# main.net
KiCad netlist of a schematic drawn in Altium Designer
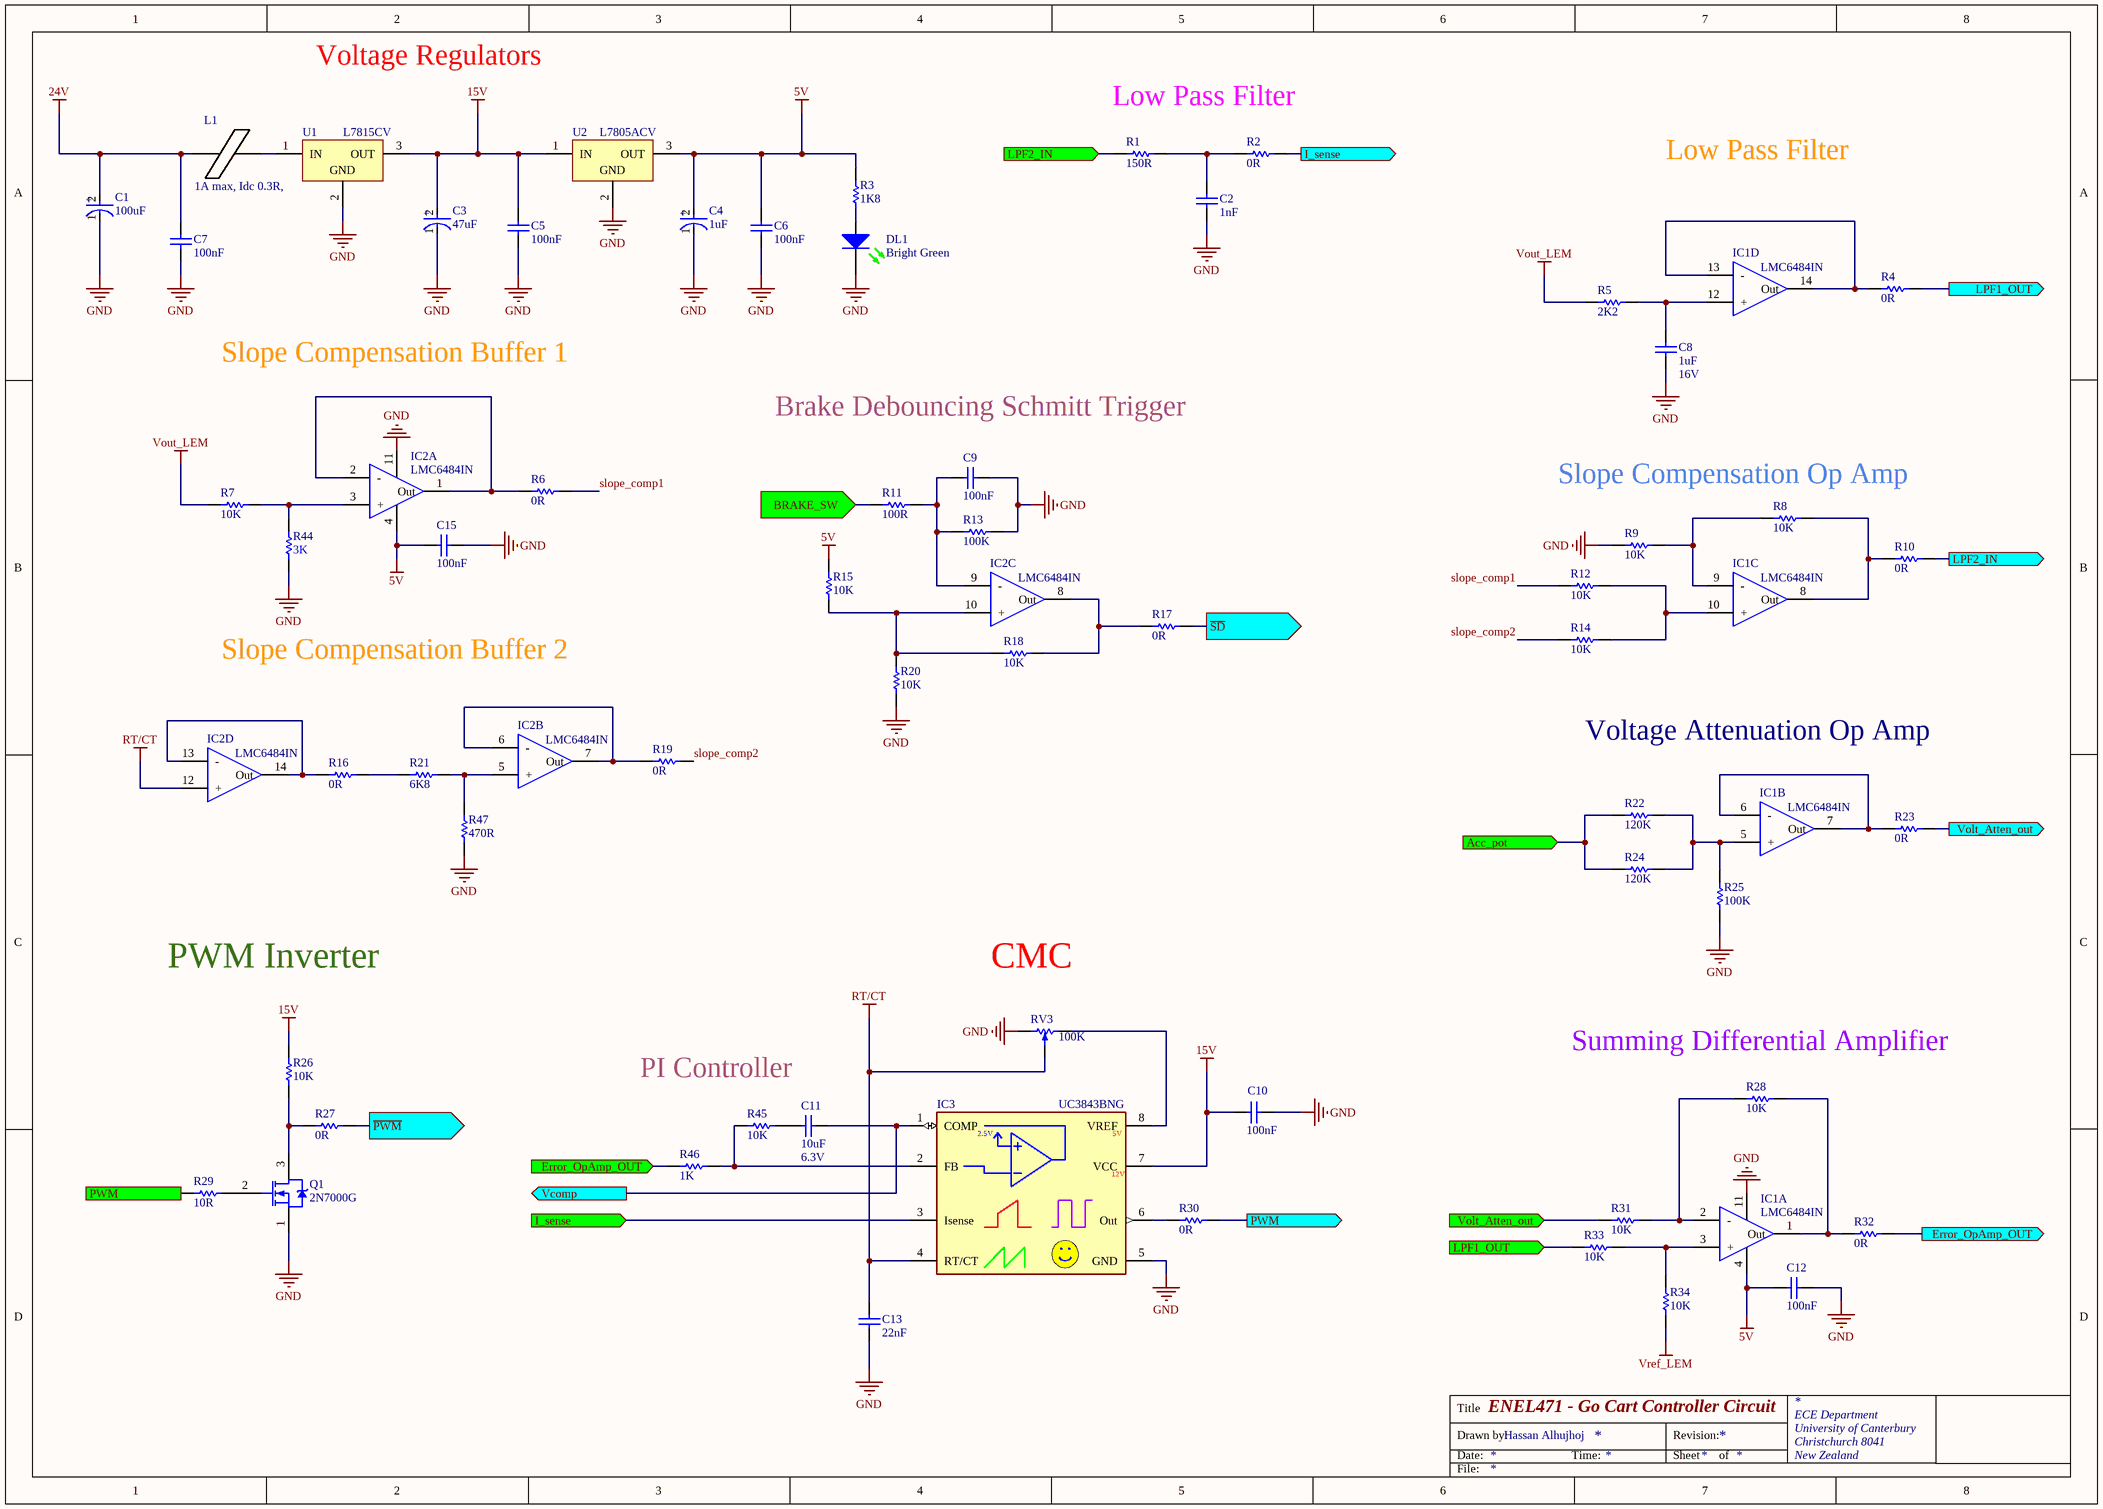
[diagram p0: main.SchDoc]

(export (version "E")
  (design (tool "Eeschema 10.0.6"))
  (components
    (comp (ref "C1")
      (value "100uF")
      (footprint "FP-ESLGM-MFG")
      (description "CAP ALUM 100UF 20% 50V THRU HOLE. Part Number: ESL107M050AGMAA. Dia: 8mm.")
      (fields
        (field (name "TOLERANCE") "20%")
        (field (name "OCTOPART") "https://octopart.com/esl107m050agmaa-kemet-84758890")
      )
      (libsource (lib "Altium Content Vault") (part "a00bbbee19879c290e62620ae7e47b1"))
    )
    (comp (ref "C2")
      (value "1nF")
      (footprint "CAPC1608L")
      (description "CAP CER 1nF X7R +-10% 50V 0603")
      (libsource (lib "ECE AD19Components_19V1") (part "CC_1nF_0603"))
    )
    (comp (ref "C3")
      (value "47uF")
      (footprint "FP-ESLE3-MFG")
      (description "CAP ALUM 10UF 20% 100V THRU HOLE. Part Number: ESL106M100AE3AA. Dia: 6.3mm.")
      (fields (field (name "TOLERANCE") "20%") (field (name "MANUFACTURER PART NUMBER") "ESL106M100AE3AA"))
      (libsource (lib "Altium Content Vault") (part "cf48714ba7e38822c1575c7ec0b6d1f"))
    )
    (comp (ref "C4")
      (value "1uF")
      (footprint "FP-UPW1E220MDD-MFG")
      (description "CAP ALUM 22UF 20% 25V RADIAL. Part Number: UPW1E220MDD. Dia: 5mm.")
      (fields
        (field (name "OCTOPART") "https://octopart.com/upw1e220mdd-nichicon-202818")
        (field (name "TOLERANCE") "20%")
      )
      (libsource (lib "Altium Content Vault") (part "cf48714ba7e38822c1575c7ec0b6d1f"))
    )
    (comp (ref "C5")
      (value "100nF")
      (footprint "CAPC1608L")
      (description "CAP CER 100nF X7R +-10% 50V 0603")
      (libsource (lib "ECE AD19Components_19V1") (part "CC_100nF_0603"))
    )
    (comp (ref "C6")
      (value "100nF")
      (footprint "CAPC1608L")
      (description "CAP CER 100nF X7R +-10% 50V 0603")
      (libsource (lib "ECE AD19Components_19V1") (part "CC_100nF_0603"))
    )
    (comp (ref "C7")
      (value "100nF")
      (footprint "CAPC1608L")
      (description "CAP CER 100nF X7R +-10% 50V 0603")
      (libsource (lib "ECE AD19Components_19V1") (part "CC_100nF_0603"))
    )
    (comp (ref "C8")
      (value "1uF")
      (footprint "CAPC1608L")
      (description "CAP CER 1uF Y5V -20% +80% 16V 0603")
      (fields (field (name "MAX VOLTAGE") "16V"))
      (libsource (lib "ECE AD19Components_19V1") (part "CC_1uF_0603"))
    )
    (comp (ref "C9")
      (value "100nF")
      (footprint "CAPC1608L")
      (description "CAP CER 100nF X7R +-10% 50V 0603")
      (libsource (lib "ECE AD19Components_19V1") (part "CC_100nF_0603"))
    )
    (comp (ref "C10")
      (value "100nF")
      (footprint "CAPC1608L")
      (description "CAP CER 100nF X7R +-10% 50V 0603")
      (libsource (lib "ECE AD19Components_19V1") (part "CC_100nF_0603"))
    )
    (comp (ref "C11")
      (value "10uF")
      (footprint "CAPC1608L")
      (description "CAP CER 10UF X5R +-20% 6V3 0603")
      (fields (field (name "VOLTAGE - RATED") "6.3V"))
      (libsource (lib "ECE AD19Components_19V1") (part "CC_10uF_0603"))
    )
    (comp (ref "C12")
      (value "100nF")
      (footprint "CAPC1608L")
      (description "CAP CER 100nF X7R +-10% 50V 0603")
      (libsource (lib "ECE AD19Components_19V1") (part "CC_100nF_0603"))
    )
    (comp (ref "C13")
      (value "22nF")
      (footprint "CAPC1608L")
      (description "CAP CER 22nF X7R +-10% 50V 0603")
      (libsource (lib "ECE AD19Components_19V1") (part "CC_22nF_0603"))
    )
    (comp (ref "C15")
      (value "100nF")
      (footprint "CAPC1608L")
      (description "CAP CER 100nF X7R +-10% 50V 0603")
      (libsource (lib "ECE AD19Components_19V1") (part "CC_100nF_0603"))
    )
    (comp (ref "DL1")
      (value "Bright Green")
      (footprint "WL-SMCW0603")
      (description "LED Bright Green 40mcd 0603 SMD")
      (fields
        (field (name "MANUFACTURER") "WURTH ELEKTRONIK")
        (field (name "MANUFACTURER PART NUMBER") "150060VS75000")
        (field (name "LED COLOUR") "Bright Green")
      )
      (libsource (lib "ECE AD19Components_19V1") (part "DL_150060VS75000"))
    )
    (comp (ref "IC1")
      (value "LMC6484IN")
      (footprint "SamacSys:DIP794W56P254L1905H533Q14N")
      (description "Integrated Circuit")
      (fields (field (name "MOUSER PART NUMBER") "926-LMC6484IN"))
      (libsource (lib "SamacSys") (part "LMC6484IN"))
    )
    (comp (ref "IC2")
      (value "LMC6484IN")
      (footprint "SamacSys:DIP794W56P254L1905H533Q14N")
      (description "Integrated Circuit")
      (fields (field (name "MOUSER PART NUMBER") "926-LMC6484IN"))
      (libsource (lib "SamacSys") (part "LMC6484IN"))
    )
    (comp (ref "IC3")
      (value "UC3843BNG")
      (footprint "SamacSys:DIP794W56P254L959H533Q8B")
      (description "Integrated Circuit")
      (fields (field (name "MOUSER PART NUMBER") "863-UC3843BNG"))
      (libsource (lib "SamacSys") (part "UC3843BNG"))
    )
    (comp (ref "L1")
      (value "1A max, Idc 0.3R,")
      (footprint "INDC3216L")
      (description "Ferrite Bead, Rdc 0.3R, Z100MHZ 600R, Imax 1A, SMD 1206")
      (fields
        (field (name "MANUFACTURER") "FAIR-RITE")
        (field (name "MANUFACTURER PART NUMBER") "2512066017Y1")
      )
      (libsource (lib "ECE AD19Components_19V1") (part "IN_Ferrite-Bead"))
    )
    (comp (ref "Q1")
      (value "2N7000G")
      (footprint "ONSC-TO-92-3-29-11")
      (description "Small Signal MOSFET, 200 mA, 60 V, N-Channel, 3-Pin TO-92, Pb-Free, Bulk Box")
      (fields (field (name "MANUFACTURER") "On Semiconductor"))
      (libsource (lib "Altium Content Vault") (part "ONSC-NMOS-S1G2D3-3"))
    )
    (comp (ref "R1")
      (value "150R")
      (footprint "RESC1608L")
      (description "RES 150 OHM 1/10W 5% 0603 SMD")
      (libsource (lib "ECE AD19Components_19V1") (part "RS_150R"))
    )
    (comp (ref "R2")
      (value "0R")
      (footprint "RESC1608L")
      (description "RES 0.0 OHM 1/10W 5% 0603 SMD")
      (libsource (lib "ECE AD19Components_19V1") (part "RS_0R0"))
    )
    (comp (ref "R3")
      (value "1K8")
      (footprint "RESC1608L")
      (description "RES 1.8K OHM 1/10W 5% 0603 SMD")
      (libsource (lib "ECE AD19Components_19V1") (part "RS_1K8"))
    )
    (comp (ref "R4")
      (value "0R")
      (footprint "RESC1608L")
      (description "RES 0.0 OHM 1/10W 5% 0603 SMD")
      (libsource (lib "ECE AD19Components_19V1") (part "RS_0R0"))
    )
    (comp (ref "R5")
      (value "2K2")
      (footprint "RESC1608L")
      (description "RES 2.2K OHM 1/10W 5% 0603 SMD")
      (libsource (lib "ECE AD19Components_19V1") (part "RS_2K2"))
    )
    (comp (ref "R6")
      (value "0R")
      (footprint "RESC1608L")
      (description "RES 0.0 OHM 1/10W 5% 0603 SMD")
      (libsource (lib "ECE AD19Components_19V1") (part "RS_0R0"))
    )
    (comp (ref "R7")
      (value "10K")
      (footprint "RESC1608L")
      (description "RES 10.0K OHM 1/10W 5% 0603 SMD")
      (libsource (lib "ECE AD19Components_19V1") (part "RS_10K"))
    )
    (comp (ref "R8")
      (value "10K")
      (footprint "RESC1608L")
      (description "RES 10.0K OHM 1/10W 5% 0603 SMD")
      (libsource (lib "ECE AD19Components_19V1") (part "RS_10K"))
    )
    (comp (ref "R9")
      (value "10K")
      (footprint "RESC1608L")
      (description "RES 10.0K OHM 1/10W 5% 0603 SMD")
      (libsource (lib "ECE AD19Components_19V1") (part "RS_10K"))
    )
    (comp (ref "R10")
      (value "0R")
      (footprint "RESC1608L")
      (description "RES 0.0 OHM 1/10W 5% 0603 SMD")
      (libsource (lib "ECE AD19Components_19V1") (part "RS_0R0"))
    )
    (comp (ref "R11")
      (value "100R")
      (footprint "RESC1608L")
      (description "RES 100 OHM 1/10W 5% 0603 SMD")
      (libsource (lib "ECE AD19Components_19V1") (part "RS_100R"))
    )
    (comp (ref "R12")
      (value "10K")
      (footprint "RESC1608L")
      (description "RES 10.0K OHM 1/10W 5% 0603 SMD")
      (libsource (lib "ECE AD19Components_19V1") (part "RS_10K"))
    )
    (comp (ref "R13")
      (value "100K")
      (footprint "RESC1608L")
      (description "RES 100K OHM 1/10W 5% 0603 SMD")
      (libsource (lib "ECE AD19Components_19V1") (part "RS_100K"))
    )
    (comp (ref "R14")
      (value "10K")
      (footprint "RESC1608L")
      (description "RES 10.0K OHM 1/10W 5% 0603 SMD")
      (libsource (lib "ECE AD19Components_19V1") (part "RS_10K"))
    )
    (comp (ref "R15")
      (value "10K")
      (footprint "RESC1608L")
      (description "RES 10.0K OHM 1/10W 5% 0603 SMD")
      (libsource (lib "ECE AD19Components_19V1") (part "RS_10K"))
    )
    (comp (ref "R16")
      (value "0R")
      (footprint "RESC1608L")
      (description "RES 0.0 OHM 1/10W 5% 0603 SMD")
      (libsource (lib "ECE AD19Components_19V1") (part "RS_0R0"))
    )
    (comp (ref "R17")
      (value "0R")
      (footprint "RESC1608L")
      (description "RES 0.0 OHM 1/10W 5% 0603 SMD")
      (libsource (lib "ECE AD19Components_19V1") (part "RS_0R0"))
    )
    (comp (ref "R18")
      (value "10K")
      (footprint "RESC1608L")
      (description "RES 10.0K OHM 1/10W 5% 0603 SMD")
      (libsource (lib "ECE AD19Components_19V1") (part "RS_10K"))
    )
    (comp (ref "R19")
      (value "0R")
      (footprint "RESC1608L")
      (description "RES 0.0 OHM 1/10W 5% 0603 SMD")
      (libsource (lib "ECE AD19Components_19V1") (part "RS_0R0"))
    )
    (comp (ref "R20")
      (value "10K")
      (footprint "RESC1608L")
      (description "RES 10.0K OHM 1/10W 5% 0603 SMD")
      (libsource (lib "ECE AD19Components_19V1") (part "RS_10K"))
    )
    (comp (ref "R21")
      (value "6K8")
      (footprint "RESC1608L")
      (description "RES 6k8 OHM 1/10W 5% 0603 SMD")
      (libsource (lib "ECE AD19Components_19V1") (part "RS_6K8"))
    )
    (comp (ref "R22")
      (value "120K")
      (footprint "RESC1608L")
      (description "RES 120K OHM 1/10W 5% 0603 SMD")
      (libsource (lib "ECE AD19Components_19V1") (part "RS_120K"))
    )
    (comp (ref "R23")
      (value "0R")
      (footprint "RESC1608L")
      (description "RES 0.0 OHM 1/10W 5% 0603 SMD")
      (libsource (lib "ECE AD19Components_19V1") (part "RS_0R0"))
    )
    (comp (ref "R24")
      (value "120K")
      (footprint "RESC1608L")
      (description "RES 120K OHM 1/10W 5% 0603 SMD")
      (libsource (lib "ECE AD19Components_19V1") (part "RS_120K"))
    )
    (comp (ref "R25")
      (value "100K")
      (footprint "RESC1608L")
      (description "RES 100K OHM 1/10W 5% 0603 SMD")
      (libsource (lib "ECE AD19Components_19V1") (part "RS_100K"))
    )
    (comp (ref "R26")
      (value "10K")
      (footprint "RESC1608L")
      (description "RES 10.0K OHM 1/10W 5% 0603 SMD")
      (libsource (lib "ECE AD19Components_19V1") (part "RS_10K"))
    )
    (comp (ref "R27")
      (value "0R")
      (footprint "RESC1608L")
      (description "RES 0.0 OHM 1/10W 5% 0603 SMD")
      (libsource (lib "ECE AD19Components_19V1") (part "RS_0R0"))
    )
    (comp (ref "R28")
      (value "10K")
      (footprint "RESC1608L")
      (description "RES 10.0K OHM 1/10W 5% 0603 SMD")
      (libsource (lib "ECE AD19Components_19V1") (part "RS_10K"))
    )
    (comp (ref "R29")
      (value "10R")
      (footprint "RESC1608L")
      (description "RES 10 OHM 1/10W 5% 0603 SMD")
      (libsource (lib "ECE AD19Components_19V1") (part "RS_10R"))
    )
    (comp (ref "R30")
      (value "0R")
      (footprint "RESC1608L")
      (description "RES 0.0 OHM 1/10W 5% 0603 SMD")
      (libsource (lib "ECE AD19Components_19V1") (part "RS_0R0"))
    )
    (comp (ref "R31")
      (value "10K")
      (footprint "RESC1608L")
      (description "RES 10.0K OHM 1/10W 5% 0603 SMD")
      (libsource (lib "ECE AD19Components_19V1") (part "RS_10K"))
    )
    (comp (ref "R32")
      (value "0R")
      (footprint "RESC1608L")
      (description "RES 0.0 OHM 1/10W 5% 0603 SMD")
      (libsource (lib "ECE AD19Components_19V1") (part "RS_0R0"))
    )
    (comp (ref "R33")
      (value "10K")
      (footprint "RESC1608L")
      (description "RES 10.0K OHM 1/10W 5% 0603 SMD")
      (libsource (lib "ECE AD19Components_19V1") (part "RS_10K"))
    )
    (comp (ref "R34")
      (value "10K")
      (footprint "RESC1608L")
      (description "RES 10.0K OHM 1/10W 5% 0603 SMD")
      (libsource (lib "ECE AD19Components_19V1") (part "RS_10K"))
    )
    (comp (ref "R44")
      (value "3K")
      (footprint "RESC1608L")
      (description "RES 3K OHM 1/10W 5% 0603 SMD")
      (libsource (lib "ECE AD19Components_19V1") (part "RS_3K"))
    )
    (comp (ref "R45")
      (value "10K")
      (footprint "RESC1608L")
      (description "RES 10.0K OHM 1/10W 5% 0603 SMD")
      (libsource (lib "ECE AD19Components_19V1") (part "RS_10K"))
    )
    (comp (ref "R46")
      (value "1K")
      (footprint "RESC1608L")
      (description "RES 1.0K OHM 1/10W 5% 0603 SMD")
      (libsource (lib "ECE AD19Components_19V1") (part "RS_1K"))
    )
    (comp (ref "R47")
      (value "470R")
      (footprint "RESC1608L")
      (description "RES 470 OHM 1/10W 5% 0603 SMD")
      (libsource (lib "ECE AD19Components_19V1") (part "RS_470R"))
    )
    (comp (ref "RV3")
      (value "100K")
      (footprint "PVZ2A")
      (description "Trim Pot SMD 100K Murata PVZ2 Series SMD")
      (fields
        (field (name "MANUFACTURER") "MURATA")
        (field (name "MANUFACTURER PART NUMBER") "PVZ2A104C04B00")
      )
      (libsource (lib "ECE AD19Components_19V1") (part "RM_100K"))
    )
    (comp (ref "U1")
      (value "L7815CV")
      (footprint "TO220")
      (description "Positive Voltage Regulator, 15V, 3-Pin TO-220")
      (libsource (lib "Altium Content Vault") (part "PM-REG-L4940-SIL3"))
    )
    (comp (ref "U2")
      (value "L7805ACV")
      (footprint "TO220")
      (description "Positive Voltage Regulator, 5V, 3-Pin TO-220")
      (libsource (lib "Altium Content Vault") (part "PM-REG-L4940-SIL3"))
    )
  )
  (nets
    (net (code "1") (name "/Acc_pot") (class "Default")
      (node (ref "R22") (pin "2") (pinfunction "2_2") (pintype "passive"))
      (node (ref "R24") (pin "1") (pinfunction "1_1") (pintype "passive"))
    )
    (net (code "2") (name "/BRAKE_SW") (class "Default")
      (node (ref "R11") (pin "1") (pinfunction "1_1") (pintype "passive"))
    )
    (net (code "3") (name "/Error_OpAmp_OUT") (class "Default")
      (node (ref "R32") (pin "2") (pinfunction "2_2") (pintype "passive"))
      (node (ref "R46") (pin "1") (pinfunction "1_1") (pintype "passive"))
    )
    (net (code "4") (name "/I_sense") (class "Default")
      (node (ref "IC3") (pin "3") (pinfunction "Isense_3") (pintype "passive"))
      (node (ref "R2") (pin "2") (pinfunction "2_2") (pintype "passive"))
    )
    (net (code "5") (name "/LPF1_OUT") (class "Default")
      (node (ref "R33") (pin "1") (pinfunction "1_1") (pintype "passive"))
      (node (ref "R4") (pin "2") (pinfunction "2_2") (pintype "passive"))
    )
    (net (code "6") (name "/LPF2_IN") (class "Default")
      (node (ref "R1") (pin "1") (pinfunction "1_1") (pintype "passive"))
      (node (ref "R10") (pin "2") (pinfunction "2_2") (pintype "passive"))
    )
    (net (code "7") (name "/PWM") (class "Default")
      (node (ref "R29") (pin "1") (pinfunction "1_1") (pintype "passive"))
      (node (ref "R30") (pin "2") (pinfunction "2_2") (pintype "passive"))
    )
    (net (code "8") (name "/Vcomp") (class "Default")
      (node (ref "C11") (pin "1") (pinfunction "1_1") (pintype "passive"))
      (node (ref "IC3") (pin "1") (pinfunction "COMP_1") (pintype "bidirectional"))
    )
    (net (code "9") (name "/Volt_Atten_out") (class "Default")
      (node (ref "R23") (pin "2") (pinfunction "2_2") (pintype "passive"))
      (node (ref "R31") (pin "1") (pinfunction "1_1") (pintype "passive"))
    )
    (net (code "10") (name "/slope_comp1") (class "Default")
      (node (ref "R12") (pin "1") (pinfunction "1_1") (pintype "passive"))
      (node (ref "R6") (pin "2") (pinfunction "2_2") (pintype "passive"))
    )
    (net (code "11") (name "/slope_comp2") (class "Default")
      (node (ref "R14") (pin "1") (pinfunction "1_1") (pintype "passive"))
      (node (ref "R19") (pin "2") (pinfunction "2_2") (pintype "passive"))
    )
    (net (code "12") (name "/~{PWM}") (class "Default")
      (node (ref "R27") (pin "2") (pinfunction "2_2") (pintype "passive"))
    )
    (net (code "13") (name "/~{SD}") (class "Default")
      (node (ref "R17") (pin "2") (pinfunction "2_2") (pintype "passive"))
    )
    (net (code "14") (name "5V") (class "Default")
      (node (ref "C12") (pin "1") (pinfunction "1_1") (pintype "passive"))
      (node (ref "C15") (pin "1") (pinfunction "1_1") (pintype "passive"))
      (node (ref "C4") (pin "2") (pinfunction "A_2") (pintype "passive"))
      (node (ref "C6") (pin "1") (pinfunction "1_1") (pintype "passive"))
      (node (ref "IC1") (pin "4") (pinfunction "Vcc_4") (pintype "power_in"))
      (node (ref "IC2") (pin "4") (pinfunction "Vcc_4") (pintype "power_in"))
      (node (ref "R15") (pin "2") (pinfunction "2_2") (pintype "passive"))
      (node (ref "R3") (pin "1") (pinfunction "1_1") (pintype "passive"))
      (node (ref "U2") (pin "3") (pinfunction "OUT_3") (pintype "power_in"))
    )
    (net (code "15") (name "15V") (class "Default")
      (node (ref "C10") (pin "1") (pinfunction "1_1") (pintype "passive"))
      (node (ref "C3") (pin "2") (pinfunction "A_2") (pintype "passive"))
      (node (ref "C5") (pin "1") (pinfunction "1_1") (pintype "passive"))
      (node (ref "IC3") (pin "7") (pinfunction "VCC_7") (pintype "power_in"))
      (node (ref "R26") (pin "2") (pinfunction "2_2") (pintype "passive"))
      (node (ref "U1") (pin "3") (pinfunction "OUT_3") (pintype "power_in"))
      (node (ref "U2") (pin "1") (pinfunction "IN_1") (pintype "power_in"))
    )
    (net (code "16") (name "24V") (class "Default")
      (node (ref "C1") (pin "2") (pinfunction "A_2") (pintype "passive"))
      (node (ref "C7") (pin "1") (pinfunction "1_1") (pintype "passive"))
      (node (ref "L1") (pin "1") (pinfunction "1_1") (pintype "passive"))
    )
    (net (code "17") (name "GND") (class "Default")
      (node (ref "C1") (pin "1") (pinfunction "C_1") (pintype "passive"))
      (node (ref "C10") (pin "2") (pinfunction "2_2") (pintype "passive"))
      (node (ref "C12") (pin "2") (pinfunction "2_2") (pintype "passive"))
      (node (ref "C13") (pin "2") (pinfunction "2_2") (pintype "passive"))
      (node (ref "C15") (pin "2") (pinfunction "2_2") (pintype "passive"))
      (node (ref "C2") (pin "1") (pinfunction "1_1") (pintype "passive"))
      (node (ref "C3") (pin "1") (pinfunction "C_1") (pintype "passive"))
      (node (ref "C4") (pin "1") (pinfunction "C_1") (pintype "passive"))
      (node (ref "C5") (pin "2") (pinfunction "2_2") (pintype "passive"))
      (node (ref "C6") (pin "2") (pinfunction "2_2") (pintype "passive"))
      (node (ref "C7") (pin "2") (pinfunction "2_2") (pintype "passive"))
      (node (ref "C8") (pin "1") (pinfunction "1_1") (pintype "passive"))
      (node (ref "C9") (pin "2") (pinfunction "2_2") (pintype "passive"))
      (node (ref "DL1") (pin "1") (pinfunction "K_1") (pintype "passive"))
      (node (ref "IC1") (pin "11") (pinfunction "-Vcc_11") (pintype "power_in"))
      (node (ref "IC2") (pin "11") (pinfunction "-Vcc_11") (pintype "power_in"))
      (node (ref "IC3") (pin "5") (pinfunction "GND_5") (pintype "power_in"))
      (node (ref "Q1") (pin "1") (pinfunction "S_1") (pintype "passive"))
      (node (ref "R13") (pin "2") (pinfunction "2_2") (pintype "passive"))
      (node (ref "R20") (pin "1") (pinfunction "1_1") (pintype "passive"))
      (node (ref "R25") (pin "1") (pinfunction "1_1") (pintype "passive"))
      (node (ref "R44") (pin "1") (pinfunction "1_1") (pintype "passive"))
      (node (ref "R47") (pin "1") (pinfunction "1_1") (pintype "passive"))
      (node (ref "R9") (pin "1") (pinfunction "1_1") (pintype "passive"))
      (node (ref "RV3") (pin "3") (pinfunction "-_3") (pintype "passive"))
      (node (ref "U1") (pin "2") (pinfunction "GND_2") (pintype "power_in"))
      (node (ref "U2") (pin "2") (pinfunction "GND_2") (pintype "power_in"))
    )
    (net (code "18") (name "Net-(C2-Pad2)") (class "Default")
      (node (ref "C2") (pin "2") (pinfunction "2_2") (pintype "passive"))
      (node (ref "R1") (pin "2") (pinfunction "2_2") (pintype "passive"))
      (node (ref "R2") (pin "1") (pinfunction "1_1") (pintype "passive"))
    )
    (net (code "19") (name "Net-(C11-Pad2)") (class "Default")
      (node (ref "C11") (pin "2") (pinfunction "2_2") (pintype "passive"))
      (node (ref "R45") (pin "2") (pinfunction "2_2") (pintype "passive"))
    )
    (net (code "20") (name "Net-(DL1-A)") (class "Default")
      (node (ref "DL1") (pin "2") (pinfunction "A_2") (pintype "passive"))
      (node (ref "R3") (pin "2") (pinfunction "2_2") (pintype "passive"))
    )
    (net (code "21") (name "Net-(IC1A-+)") (class "Default")
      (node (ref "IC1") (pin "3") (pinfunction "+_3") (pintype "passive"))
      (node (ref "R33") (pin "2") (pinfunction "2_2") (pintype "passive"))
      (node (ref "R34") (pin "2") (pinfunction "2_2") (pintype "passive"))
    )
    (net (code "22") (name "Net-(IC1A--)") (class "Default")
      (node (ref "IC1") (pin "2") (pinfunction "-_2") (pintype "passive"))
      (node (ref "R28") (pin "1") (pinfunction "1_1") (pintype "passive"))
      (node (ref "R31") (pin "2") (pinfunction "2_2") (pintype "passive"))
    )
    (net (code "23") (name "Net-(IC1A-Out)") (class "Default")
      (node (ref "IC1") (pin "1") (pinfunction "Out_1") (pintype "passive"))
      (node (ref "R28") (pin "2") (pinfunction "2_2") (pintype "passive"))
      (node (ref "R32") (pin "1") (pinfunction "1_1") (pintype "passive"))
    )
    (net (code "24") (name "Net-(IC1B-+)") (class "Default")
      (node (ref "IC1") (pin "5") (pinfunction "+_5") (pintype "passive"))
      (node (ref "R22") (pin "1") (pinfunction "1_1") (pintype "passive"))
      (node (ref "R24") (pin "2") (pinfunction "2_2") (pintype "passive"))
      (node (ref "R25") (pin "2") (pinfunction "2_2") (pintype "passive"))
    )
    (net (code "25") (name "Net-(IC1B--)") (class "Default")
      (node (ref "IC1") (pin "6") (pinfunction "-_6") (pintype "passive"))
      (node (ref "IC1") (pin "7") (pinfunction "Out_7") (pintype "passive"))
      (node (ref "R23") (pin "1") (pinfunction "1_1") (pintype "passive"))
    )
    (net (code "26") (name "Net-(IC1C-+)") (class "Default")
      (node (ref "IC1") (pin "10") (pinfunction "+_10") (pintype "passive"))
      (node (ref "R12") (pin "2") (pinfunction "2_2") (pintype "passive"))
      (node (ref "R14") (pin "2") (pinfunction "2_2") (pintype "passive"))
    )
    (net (code "27") (name "Net-(IC1C--)") (class "Default")
      (node (ref "IC1") (pin "9") (pinfunction "-_9") (pintype "passive"))
      (node (ref "R8") (pin "1") (pinfunction "1_1") (pintype "passive"))
      (node (ref "R9") (pin "2") (pinfunction "2_2") (pintype "passive"))
    )
    (net (code "28") (name "Net-(IC1C-Out)") (class "Default")
      (node (ref "IC1") (pin "8") (pinfunction "Out_8") (pintype "passive"))
      (node (ref "R10") (pin "1") (pinfunction "1_1") (pintype "passive"))
      (node (ref "R8") (pin "2") (pinfunction "2_2") (pintype "passive"))
    )
    (net (code "29") (name "Net-(IC1D-+)") (class "Default")
      (node (ref "C8") (pin "2") (pinfunction "2_2") (pintype "passive"))
      (node (ref "IC1") (pin "12") (pinfunction "+_12") (pintype "passive"))
      (node (ref "R5") (pin "1") (pinfunction "1_1") (pintype "passive"))
    )
    (net (code "30") (name "Net-(IC1D--)") (class "Default")
      (node (ref "IC1") (pin "13") (pinfunction "-_13") (pintype "passive"))
      (node (ref "IC1") (pin "14") (pinfunction "Out_14") (pintype "passive"))
      (node (ref "R4") (pin "1") (pinfunction "1_1") (pintype "passive"))
    )
    (net (code "31") (name "Net-(IC2A-+)") (class "Default")
      (node (ref "IC2") (pin "3") (pinfunction "+_3") (pintype "passive"))
      (node (ref "R44") (pin "2") (pinfunction "2_2") (pintype "passive"))
      (node (ref "R7") (pin "2") (pinfunction "2_2") (pintype "passive"))
    )
    (net (code "32") (name "Net-(IC2A--)") (class "Default")
      (node (ref "IC2") (pin "1") (pinfunction "Out_1") (pintype "passive"))
      (node (ref "IC2") (pin "2") (pinfunction "-_2") (pintype "passive"))
      (node (ref "R6") (pin "1") (pinfunction "1_1") (pintype "passive"))
    )
    (net (code "33") (name "Net-(IC2B-+)") (class "Default")
      (node (ref "IC2") (pin "5") (pinfunction "+_5") (pintype "passive"))
      (node (ref "R21") (pin "2") (pinfunction "2_2") (pintype "passive"))
      (node (ref "R47") (pin "2") (pinfunction "2_2") (pintype "passive"))
    )
    (net (code "34") (name "Net-(IC2B--)") (class "Default")
      (node (ref "IC2") (pin "6") (pinfunction "-_6") (pintype "passive"))
      (node (ref "IC2") (pin "7") (pinfunction "Out_7") (pintype "passive"))
      (node (ref "R19") (pin "1") (pinfunction "1_1") (pintype "passive"))
    )
    (net (code "35") (name "Net-(IC2C-+)") (class "Default")
      (node (ref "IC2") (pin "10") (pinfunction "+_10") (pintype "passive"))
      (node (ref "R15") (pin "1") (pinfunction "1_1") (pintype "passive"))
      (node (ref "R18") (pin "1") (pinfunction "1_1") (pintype "passive"))
      (node (ref "R20") (pin "2") (pinfunction "2_2") (pintype "passive"))
    )
    (net (code "36") (name "Net-(IC2C--)") (class "Default")
      (node (ref "C9") (pin "1") (pinfunction "1_1") (pintype "passive"))
      (node (ref "IC2") (pin "9") (pinfunction "-_9") (pintype "passive"))
      (node (ref "R11") (pin "2") (pinfunction "2_2") (pintype "passive"))
      (node (ref "R13") (pin "1") (pinfunction "1_1") (pintype "passive"))
    )
    (net (code "37") (name "Net-(IC2C-Out)") (class "Default")
      (node (ref "IC2") (pin "8") (pinfunction "Out_8") (pintype "passive"))
      (node (ref "R17") (pin "1") (pinfunction "1_1") (pintype "passive"))
      (node (ref "R18") (pin "2") (pinfunction "2_2") (pintype "passive"))
    )
    (net (code "38") (name "Net-(IC2D--)") (class "Default")
      (node (ref "IC2") (pin "13") (pinfunction "-_13") (pintype "passive"))
      (node (ref "IC2") (pin "14") (pinfunction "Out_14") (pintype "passive"))
      (node (ref "R16") (pin "1") (pinfunction "1_1") (pintype "passive"))
    )
    (net (code "39") (name "Net-(IC3-FB)") (class "Default")
      (node (ref "IC3") (pin "2") (pinfunction "FB_2") (pintype "passive"))
      (node (ref "R45") (pin "1") (pinfunction "1_1") (pintype "passive"))
      (node (ref "R46") (pin "2") (pinfunction "2_2") (pintype "passive"))
    )
    (net (code "40") (name "Net-(IC3-Out)") (class "Default")
      (node (ref "IC3") (pin "6") (pinfunction "Out_6") (pintype "output"))
      (node (ref "R30") (pin "1") (pinfunction "1_1") (pintype "passive"))
    )
    (net (code "41") (name "Net-(IC3-VREF)") (class "Default")
      (node (ref "IC3") (pin "8") (pinfunction "VREF_8") (pintype "power_in"))
      (node (ref "RV3") (pin "1") (pinfunction "1_1") (pintype "passive"))
    )
    (net (code "42") (name "Net-(Q1-D)") (class "Default")
      (node (ref "Q1") (pin "3") (pinfunction "D_3") (pintype "passive"))
      (node (ref "R26") (pin "1") (pinfunction "1_1") (pintype "passive"))
      (node (ref "R27") (pin "1") (pinfunction "1_1") (pintype "passive"))
    )
    (net (code "43") (name "Net-(Q1-G)") (class "Default")
      (node (ref "Q1") (pin "2") (pinfunction "G_2") (pintype "passive"))
      (node (ref "R29") (pin "2") (pinfunction "2_2") (pintype "passive"))
    )
    (net (code "44") (name "Net-(R16-Pad2)") (class "Default")
      (node (ref "R16") (pin "2") (pinfunction "2_2") (pintype "passive"))
      (node (ref "R21") (pin "1") (pinfunction "1_1") (pintype "passive"))
    )
    (net (code "45") (name "Net-(U1-IN)") (class "Default")
      (node (ref "L1") (pin "2") (pinfunction "2_2") (pintype "passive"))
      (node (ref "U1") (pin "1") (pinfunction "IN_1") (pintype "power_in"))
    )
    (net (code "46") (name "RT{slash}CT") (class "Default")
      (node (ref "C13") (pin "1") (pinfunction "1_1") (pintype "passive"))
      (node (ref "IC2") (pin "12") (pinfunction "+_12") (pintype "passive"))
      (node (ref "IC3") (pin "4") (pinfunction "RT/CT_4") (pintype "passive"))
      (node (ref "RV3") (pin "2") (pinfunction "W_2") (pintype "passive"))
    )
    (net (code "47") (name "Vout_LEM") (class "Default")
      (node (ref "R5") (pin "2") (pinfunction "2_2") (pintype "passive"))
      (node (ref "R7") (pin "1") (pinfunction "1_1") (pintype "passive"))
    )
    (net (code "48") (name "Vref_LEM") (class "Default")
      (node (ref "R34") (pin "1") (pinfunction "1_1") (pintype "passive"))
    )
  )
)
